# trans48.net
KiCad netlist of a schematic drawn in EAGLE
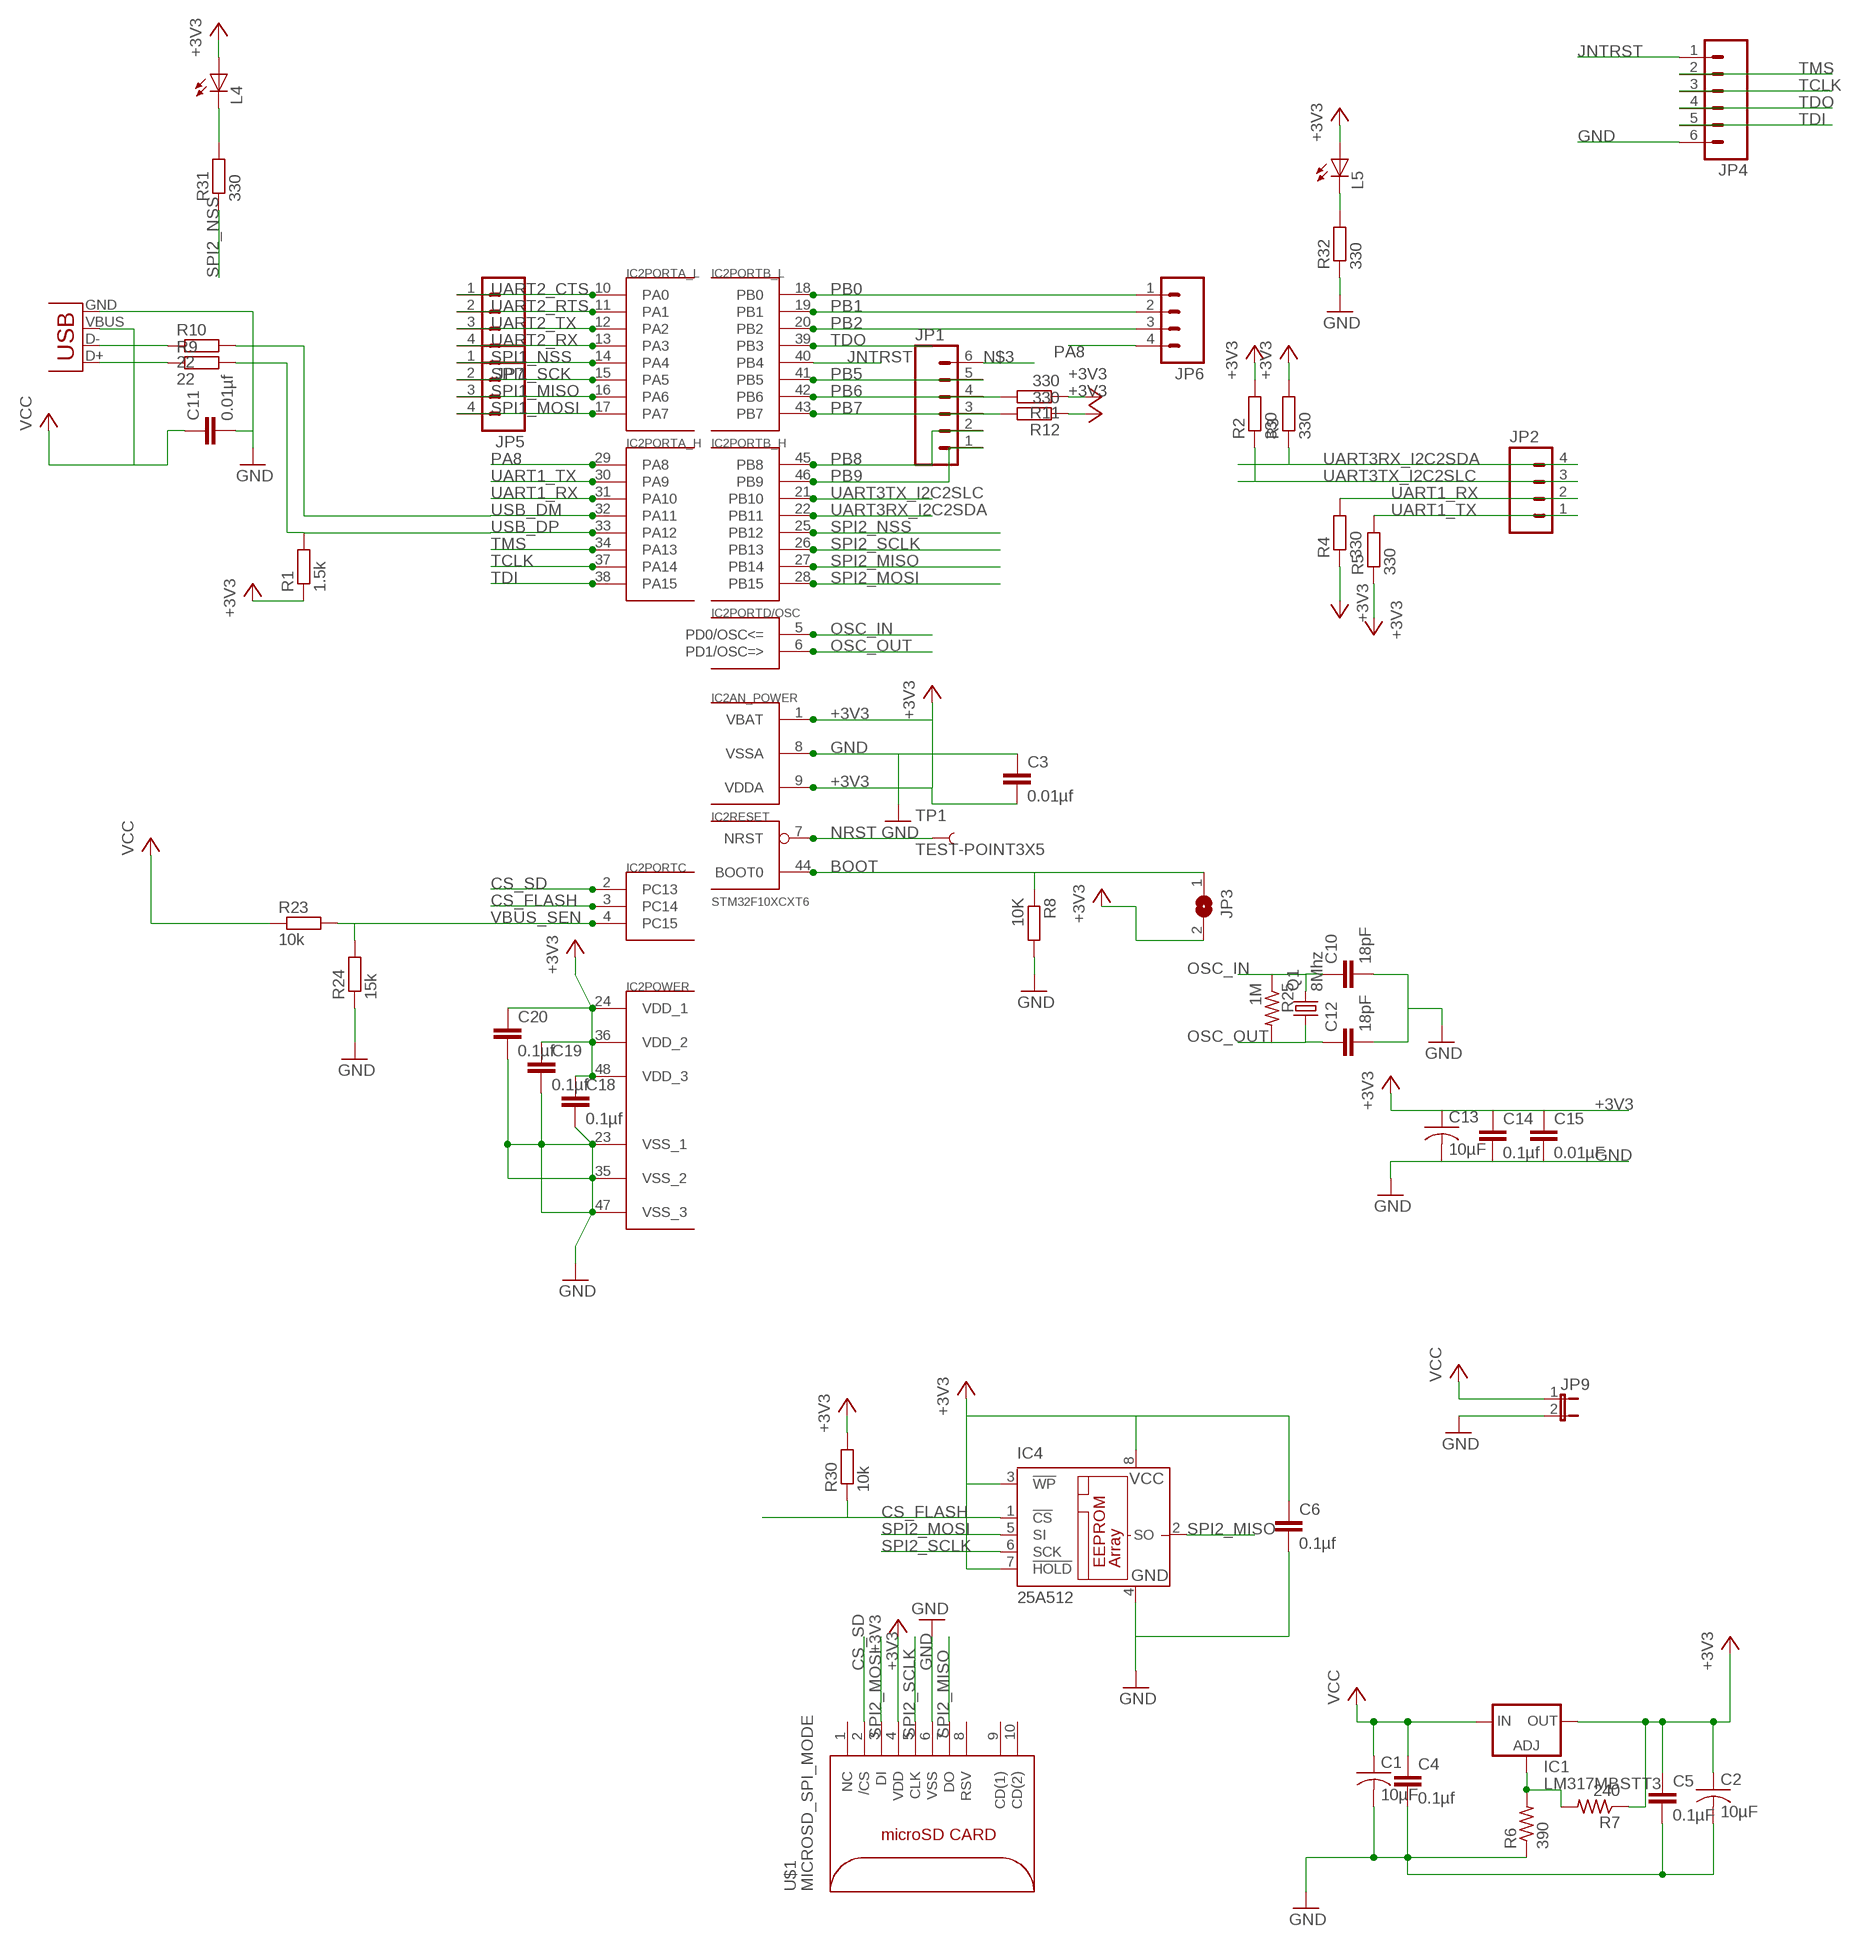
[diagram p0: schematic, sheet 1]

(export (version "E")
  (design (tool "Eeschema 10.0.6"))
  (components
    (comp (ref "C1")
      (value "10µF")
      (footprint "eagle-import:C1206")
      (libsource (lib "eagle-import") (part "C-USC1206"))
    )
    (comp (ref "C2")
      (value "10µF")
      (footprint "eagle-import:C1206")
      (libsource (lib "eagle-import") (part "C-USC1206"))
    )
    (comp (ref "C3")
      (value "0.01µf")
      (footprint "eagle-import:C0402")
      (libsource (lib "eagle-import") (part "C-EUC0402"))
    )
    (comp (ref "C4")
      (value "0.1µf")
      (footprint "eagle-import:C0402")
      (libsource (lib "eagle-import") (part "C-EUC0402"))
    )
    (comp (ref "C5")
      (value "0.1µF")
      (footprint "eagle-import:C0402")
      (libsource (lib "eagle-import") (part "C-EUC0402"))
    )
    (comp (ref "C6")
      (value "0.1µf")
      (footprint "eagle-import:C0402")
      (libsource (lib "eagle-import") (part "C-EUC0402"))
    )
    (comp (ref "C10")
      (value "18pF")
      (footprint "eagle-import:C0603")
      (libsource (lib "eagle-import") (part "C-EUC0603"))
    )
    (comp (ref "C11")
      (value "0.01µf")
      (footprint "eagle-import:C0402")
      (libsource (lib "eagle-import") (part "C-EUC0402"))
    )
    (comp (ref "C12")
      (value "18pF")
      (footprint "eagle-import:C0603")
      (libsource (lib "eagle-import") (part "C-EUC0603"))
    )
    (comp (ref "C13")
      (value "10µF")
      (footprint "eagle-import:C1206")
      (libsource (lib "eagle-import") (part "C-USC1206"))
    )
    (comp (ref "C14")
      (value "0.1µf")
      (footprint "eagle-import:C0603")
      (libsource (lib "eagle-import") (part "C-EUC0603"))
    )
    (comp (ref "C15")
      (value "0.01µF")
      (footprint "eagle-import:C0603")
      (libsource (lib "eagle-import") (part "C-EUC0603"))
    )
    (comp (ref "C18")
      (value "0.1µf")
      (footprint "eagle-import:C0402")
      (libsource (lib "eagle-import") (part "C-EUC0402"))
    )
    (comp (ref "C19")
      (value "0.1µf")
      (footprint "eagle-import:C0402")
      (libsource (lib "eagle-import") (part "C-EUC0402"))
    )
    (comp (ref "C20")
      (value "0.1µf")
      (footprint "eagle-import:C0402")
      (libsource (lib "eagle-import") (part "C-EUC0402"))
    )
    (comp (ref "IC1")
      (value "LM317MBSTT3")
      (footprint "eagle-import:SOT223")
      (libsource (lib "eagle-import") (part "LM317?MBSTT3"))
    )
    (comp (ref "IC2")
      (value "STM32F10XCXT6")
      (footprint "eagle-import:TQFP48")
      (libsource (lib "eagle-import") (part "STM32F10XCXT6"))
    )
    (comp (ref "IC4")
      (value "25A512")
      (footprint "eagle-import:SO-08")
      (libsource (lib "eagle-import") (part "25SNAA080"))
    )
    (comp (ref "JP1")
      (value "M06EM406")
      (footprint "eagle-import:EM406")
      (libsource (lib "eagle-import") (part "M06EM406"))
    )
    (comp (ref "JP2")
      (value "M04SMD2")
      (footprint "eagle-import:1X04-1MM-RA")
      (libsource (lib "eagle-import") (part "M04SMD2"))
    )
    (comp (ref "JP3") (value "SJ") (footprint "eagle-import:SJ") (libsource (lib "eagle-import") (part "SJ")))
    (comp (ref "JP4")
      (value "M06EM406")
      (footprint "eagle-import:EM406")
      (libsource (lib "eagle-import") (part "M06EM406"))
    )
    (comp (ref "JP5")
      (value "M04SMD2")
      (footprint "eagle-import:1X04-1MM-RA")
      (libsource (lib "eagle-import") (part "M04SMD2"))
    )
    (comp (ref "JP6")
      (value "M04SMD2")
      (footprint "eagle-import:1X04-1MM-RA")
      (libsource (lib "eagle-import") (part "M04SMD2"))
    )
    (comp (ref "JP7")
      (value "M04SMD2")
      (footprint "eagle-import:1X04-1MM-RA")
      (libsource (lib "eagle-import") (part "M04SMD2"))
    )
    (comp (ref "JP9")
      (value "JUMPER-2SMD-NO-NS")
      (footprint "eagle-import:SJ_2S-NO-NS")
      (libsource (lib "eagle-import") (part "JUMPER-2SMD-NO-NS"))
    )
    (comp (ref "L4")
      (value "LEDSML0603")
      (footprint "eagle-import:SML0603")
      (libsource (lib "eagle-import") (part "LEDSML0603"))
    )
    (comp (ref "L5")
      (value "LEDSML0603")
      (footprint "eagle-import:SML0603")
      (libsource (lib "eagle-import") (part "LEDSML0603"))
    )
    (comp (ref "Q1")
      (value "8Mhz")
      (footprint "eagle-import:SM49")
      (libsource (lib "eagle-import") (part "CRYSTALSM49"))
    )
    (comp (ref "R1")
      (value "1.5k")
      (footprint "eagle-import:R0402")
      (libsource (lib "eagle-import") (part "R-EU_R0402"))
    )
    (comp (ref "R2")
      (value "330")
      (footprint "eagle-import:R0402")
      (libsource (lib "eagle-import") (part "R-EU_R0402"))
    )
    (comp (ref "R3")
      (value "330")
      (footprint "eagle-import:R0402")
      (libsource (lib "eagle-import") (part "R-EU_R0402"))
    )
    (comp (ref "R4")
      (value "330")
      (footprint "eagle-import:R0402")
      (libsource (lib "eagle-import") (part "R-EU_R0402"))
    )
    (comp (ref "R5")
      (value "330")
      (footprint "eagle-import:R0402")
      (libsource (lib "eagle-import") (part "R-EU_R0402"))
    )
    (comp (ref "R6")
      (value "390")
      (footprint "eagle-import:R0603")
      (libsource (lib "eagle-import") (part "R-US_R0603"))
    )
    (comp (ref "R7")
      (value "240")
      (footprint "eagle-import:R0603")
      (libsource (lib "eagle-import") (part "R-US_R0603"))
    )
    (comp (ref "R8")
      (value "10K")
      (footprint "eagle-import:R0402")
      (libsource (lib "eagle-import") (part "R-EU_R0402"))
    )
    (comp (ref "R9")
      (value "22")
      (footprint "eagle-import:R0402")
      (libsource (lib "eagle-import") (part "R-EU_R0402"))
    )
    (comp (ref "R10")
      (value "22")
      (footprint "eagle-import:R0402")
      (libsource (lib "eagle-import") (part "R-EU_R0402"))
    )
    (comp (ref "R11")
      (value "330")
      (footprint "eagle-import:R0402")
      (libsource (lib "eagle-import") (part "R-EU_R0402"))
    )
    (comp (ref "R12")
      (value "330")
      (footprint "eagle-import:R0402")
      (libsource (lib "eagle-import") (part "R-EU_R0402"))
    )
    (comp (ref "R23")
      (value "10k")
      (footprint "eagle-import:R0402")
      (libsource (lib "eagle-import") (part "R-EU_R0402"))
    )
    (comp (ref "R24")
      (value "15k")
      (footprint "eagle-import:R0402")
      (libsource (lib "eagle-import") (part "R-EU_R0402"))
    )
    (comp (ref "R25")
      (value "1M")
      (footprint "eagle-import:R0603")
      (libsource (lib "eagle-import") (part "R-US_R0603"))
    )
    (comp (ref "R30")
      (value "10k")
      (footprint "eagle-import:R0402")
      (libsource (lib "eagle-import") (part "R-EU_R0402"))
    )
    (comp (ref "R31")
      (value "330")
      (footprint "eagle-import:R0402")
      (libsource (lib "eagle-import") (part "R-EU_R0402"))
    )
    (comp (ref "R32")
      (value "330")
      (footprint "eagle-import:R0402")
      (libsource (lib "eagle-import") (part "R-EU_R0402"))
    )
    (comp (ref "TP1")
      (value "TEST-POINT3X5")
      (footprint "eagle-import:PAD.03X.05")
      (libsource (lib "eagle-import") (part "TEST-POINT3X5"))
    )
    (comp (ref "U$1")
      (value "MICROSD_SPI_MODE")
      (footprint "eagle-import:MICRO_SD_CONNECTOR")
      (libsource (lib "eagle-import") (part "MICROSD_SPI_MODE"))
    )
    (comp (ref "X1")
      (value "USB-MICROB")
      (footprint "eagle-import:USB-MICROB")
      (libsource (lib "eagle-import") (part "USB-MICROB"))
    )
  )
  (nets
    (net (code "1") (name "+3V3") (class "Default")
      (node (ref "C13") (pin "1") (pinfunction "1_1") (pintype "passive"))
      (node (ref "C14") (pin "1") (pinfunction "1_1") (pintype "passive"))
      (node (ref "C15") (pin "1") (pinfunction "1_1") (pintype "passive"))
      (node (ref "C18") (pin "1") (pinfunction "1_1") (pintype "passive"))
      (node (ref "C19") (pin "1") (pinfunction "1_1") (pintype "passive"))
      (node (ref "C2") (pin "1") (pinfunction "1_1") (pintype "passive"))
      (node (ref "C20") (pin "1") (pinfunction "1_1") (pintype "passive"))
      (node (ref "C3") (pin "2") (pinfunction "2_2") (pintype "passive"))
      (node (ref "C5") (pin "1") (pinfunction "1_1") (pintype "passive"))
      (node (ref "C6") (pin "1") (pinfunction "1_1") (pintype "passive"))
      (node (ref "IC1") (pin "4") (pinfunction "OUT_4") (pintype "passive"))
      (node (ref "IC2") (pin "1") (pinfunction "VBAT_1") (pintype "power_in"))
      (node (ref "IC2") (pin "24") (pinfunction "VDD_1_24") (pintype "power_in"))
      (node (ref "IC2") (pin "36") (pinfunction "VDD_2_36") (pintype "power_in"))
      (node (ref "IC2") (pin "48") (pinfunction "VDD_3_48") (pintype "power_in"))
      (node (ref "IC2") (pin "9") (pinfunction "VDDA_9") (pintype "power_in"))
      (node (ref "IC4") (pin "3") (pinfunction "~{WP}_3") (pintype "input"))
      (node (ref "IC4") (pin "7") (pinfunction "~{HOLD}_7") (pintype "input"))
      (node (ref "IC4") (pin "8") (pinfunction "VCC_8") (pintype "power_in"))
      (node (ref "JP3") (pin "2") (pinfunction "2_2") (pintype "passive"))
      (node (ref "L4") (pin "A") (pinfunction "A_A") (pintype "passive"))
      (node (ref "L5") (pin "A") (pinfunction "A_A") (pintype "passive"))
      (node (ref "R1") (pin "1") (pinfunction "1_1") (pintype "passive"))
      (node (ref "R11") (pin "1") (pinfunction "1_1") (pintype "passive"))
      (node (ref "R12") (pin "1") (pinfunction "1_1") (pintype "passive"))
      (node (ref "R2") (pin "2") (pinfunction "2_2") (pintype "passive"))
      (node (ref "R3") (pin "2") (pinfunction "2_2") (pintype "passive"))
      (node (ref "R30") (pin "2") (pinfunction "2_2") (pintype "passive"))
      (node (ref "R4") (pin "1") (pinfunction "1_1") (pintype "passive"))
      (node (ref "R5") (pin "1") (pinfunction "1_1") (pintype "passive"))
      (node (ref "R7") (pin "1") (pinfunction "1_1") (pintype "passive"))
      (node (ref "U$1") (pin "4") (pinfunction "VDD_4") (pintype "bidirectional"))
    )
    (net (code "2") (name "/BOOT") (class "Default")
      (node (ref "IC2") (pin "44") (pinfunction "BOOT0_44") (pintype "input"))
      (node (ref "JP3") (pin "1") (pinfunction "1_1") (pintype "passive"))
      (node (ref "R8") (pin "1") (pinfunction "1_1") (pintype "passive"))
    )
    (net (code "3") (name "/CS_FLASH") (class "Default")
      (node (ref "IC2") (pin "3") (pinfunction "PC14_3") (pintype "bidirectional"))
      (node (ref "IC4") (pin "1") (pinfunction "~{CS}_1") (pintype "input"))
      (node (ref "R30") (pin "1") (pinfunction "1_1") (pintype "passive"))
    )
    (net (code "4") (name "/CS_SD") (class "Default")
      (node (ref "IC2") (pin "2") (pinfunction "PC13_2") (pintype "bidirectional"))
      (node (ref "U$1") (pin "2") (pinfunction "/CS_2") (pintype "bidirectional"))
    )
    (net (code "5") (name "/JNTRST") (class "Default")
      (node (ref "IC2") (pin "40") (pinfunction "PB4_40") (pintype "bidirectional"))
      (node (ref "JP4") (pin "1") (pinfunction "1_1") (pintype "passive"))
    )
    (net (code "6") (name "/N$3") (class "Default")
      (node (ref "JP1") (pin "6") (pinfunction "6_6") (pintype "passive"))
    )
    (net (code "7") (name "/NRST") (class "Default")
      (node (ref "IC2") (pin "7") (pinfunction "NRST_7") (pintype "input"))
      (node (ref "TP1") (pin "P$1") (pinfunction "1_P$1") (pintype "bidirectional"))
    )
    (net (code "8") (name "/OSC_IN") (class "Default")
      (node (ref "C10") (pin "1") (pinfunction "1_1") (pintype "passive"))
      (node (ref "IC2") (pin "5") (pinfunction "PD0/OSC<=_5") (pintype "bidirectional"))
      (node (ref "Q1") (pin "2") (pinfunction "2_2") (pintype "passive"))
      (node (ref "R25") (pin "1") (pinfunction "1_1") (pintype "passive"))
    )
    (net (code "9") (name "/OSC_OUT") (class "Default")
      (node (ref "C12") (pin "1") (pinfunction "1_1") (pintype "passive"))
      (node (ref "IC2") (pin "6") (pinfunction "PD1/OSC=>_6") (pintype "bidirectional"))
      (node (ref "Q1") (pin "1") (pinfunction "1_1") (pintype "passive"))
      (node (ref "R25") (pin "2") (pinfunction "2_2") (pintype "passive"))
    )
    (net (code "10") (name "/PA8") (class "Default")
      (node (ref "IC2") (pin "29") (pinfunction "PA8_29") (pintype "bidirectional"))
      (node (ref "JP6") (pin "4") (pinfunction "4_4") (pintype "passive"))
    )
    (net (code "11") (name "/PB0") (class "Default")
      (node (ref "IC2") (pin "18") (pinfunction "PB0_18") (pintype "bidirectional"))
      (node (ref "JP6") (pin "1") (pinfunction "1_1") (pintype "passive"))
    )
    (net (code "12") (name "/PB1") (class "Default")
      (node (ref "IC2") (pin "19") (pinfunction "PB1_19") (pintype "bidirectional"))
      (node (ref "JP6") (pin "2") (pinfunction "2_2") (pintype "passive"))
    )
    (net (code "13") (name "/PB2") (class "Default")
      (node (ref "IC2") (pin "20") (pinfunction "PB2_20") (pintype "bidirectional"))
      (node (ref "JP6") (pin "3") (pinfunction "3_3") (pintype "passive"))
    )
    (net (code "14") (name "/PB5") (class "Default")
      (node (ref "IC2") (pin "41") (pinfunction "PB5_41") (pintype "bidirectional"))
      (node (ref "JP1") (pin "5") (pinfunction "5_5") (pintype "passive"))
    )
    (net (code "15") (name "/PB6") (class "Default")
      (node (ref "IC2") (pin "42") (pinfunction "PB6_42") (pintype "bidirectional"))
      (node (ref "JP1") (pin "4") (pinfunction "4_4") (pintype "passive"))
      (node (ref "R11") (pin "2") (pinfunction "2_2") (pintype "passive"))
    )
    (net (code "16") (name "/PB7") (class "Default")
      (node (ref "IC2") (pin "43") (pinfunction "PB7_43") (pintype "bidirectional"))
      (node (ref "JP1") (pin "3") (pinfunction "3_3") (pintype "passive"))
      (node (ref "R12") (pin "2") (pinfunction "2_2") (pintype "passive"))
    )
    (net (code "17") (name "/PB8") (class "Default")
      (node (ref "IC2") (pin "45") (pinfunction "PB8_45") (pintype "bidirectional"))
      (node (ref "JP1") (pin "2") (pinfunction "2_2") (pintype "passive"))
    )
    (net (code "18") (name "/PB9") (class "Default")
      (node (ref "IC2") (pin "46") (pinfunction "PB9_46") (pintype "bidirectional"))
      (node (ref "JP1") (pin "1") (pinfunction "1_1") (pintype "passive"))
    )
    (net (code "19") (name "/SPI1_MISO") (class "Default")
      (node (ref "IC2") (pin "16") (pinfunction "PA6_16") (pintype "bidirectional"))
      (node (ref "JP5") (pin "3") (pinfunction "3_3") (pintype "passive"))
    )
    (net (code "20") (name "/SPI1_MOSI") (class "Default")
      (node (ref "IC2") (pin "17") (pinfunction "PA7_17") (pintype "bidirectional"))
      (node (ref "JP5") (pin "4") (pinfunction "4_4") (pintype "passive"))
    )
    (net (code "21") (name "/SPI1_NSS") (class "Default")
      (node (ref "IC2") (pin "14") (pinfunction "PA4_14") (pintype "bidirectional"))
      (node (ref "JP5") (pin "1") (pinfunction "1_1") (pintype "passive"))
    )
    (net (code "22") (name "/SPI1_SCK") (class "Default")
      (node (ref "IC2") (pin "15") (pinfunction "PA5_15") (pintype "bidirectional"))
      (node (ref "JP5") (pin "2") (pinfunction "2_2") (pintype "passive"))
    )
    (net (code "23") (name "/SPI2_MISO") (class "Default")
      (node (ref "IC2") (pin "27") (pinfunction "PB14_27") (pintype "bidirectional"))
      (node (ref "IC4") (pin "2") (pinfunction "SO_2") (pintype "bidirectional"))
      (node (ref "U$1") (pin "7") (pinfunction "DO_7") (pintype "bidirectional"))
    )
    (net (code "24") (name "/SPI2_MOSI") (class "Default")
      (node (ref "IC2") (pin "28") (pinfunction "PB15_28") (pintype "bidirectional"))
      (node (ref "IC4") (pin "5") (pinfunction "SI_5") (pintype "input"))
      (node (ref "U$1") (pin "3") (pinfunction "DI_3") (pintype "bidirectional"))
    )
    (net (code "25") (name "/SPI2_NSS") (class "Default")
      (node (ref "IC2") (pin "25") (pinfunction "PB12_25") (pintype "bidirectional"))
      (node (ref "R31") (pin "1") (pinfunction "1_1") (pintype "passive"))
    )
    (net (code "26") (name "/SPI2_SCLK") (class "Default")
      (node (ref "IC2") (pin "26") (pinfunction "PB13_26") (pintype "bidirectional"))
      (node (ref "IC4") (pin "6") (pinfunction "SCK_6") (pintype "input"))
      (node (ref "U$1") (pin "5") (pinfunction "CLK_5") (pintype "bidirectional"))
    )
    (net (code "27") (name "/TCLK") (class "Default")
      (node (ref "IC2") (pin "37") (pinfunction "PA14_37") (pintype "bidirectional"))
      (node (ref "JP4") (pin "3") (pinfunction "3_3") (pintype "passive"))
    )
    (net (code "28") (name "/TDI") (class "Default")
      (node (ref "IC2") (pin "38") (pinfunction "PA15_38") (pintype "bidirectional"))
      (node (ref "JP4") (pin "5") (pinfunction "5_5") (pintype "passive"))
    )
    (net (code "29") (name "/TDO") (class "Default")
      (node (ref "IC2") (pin "39") (pinfunction "PB3_39") (pintype "bidirectional"))
      (node (ref "JP4") (pin "4") (pinfunction "4_4") (pintype "passive"))
    )
    (net (code "30") (name "/TMS") (class "Default")
      (node (ref "IC2") (pin "34") (pinfunction "PA13_34") (pintype "bidirectional"))
      (node (ref "JP4") (pin "2") (pinfunction "2_2") (pintype "passive"))
    )
    (net (code "31") (name "/UART1_RX") (class "Default")
      (node (ref "IC2") (pin "31") (pinfunction "PA10_31") (pintype "bidirectional"))
      (node (ref "JP2") (pin "2") (pinfunction "2_2") (pintype "passive"))
      (node (ref "R4") (pin "2") (pinfunction "2_2") (pintype "passive"))
    )
    (net (code "32") (name "/UART1_TX") (class "Default")
      (node (ref "IC2") (pin "30") (pinfunction "PA9_30") (pintype "bidirectional"))
      (node (ref "JP2") (pin "1") (pinfunction "1_1") (pintype "passive"))
      (node (ref "R5") (pin "2") (pinfunction "2_2") (pintype "passive"))
    )
    (net (code "33") (name "/UART2_CTS") (class "Default")
      (node (ref "IC2") (pin "10") (pinfunction "PA0_10") (pintype "bidirectional"))
      (node (ref "JP7") (pin "1") (pinfunction "1_1") (pintype "passive"))
    )
    (net (code "34") (name "/UART2_RTS") (class "Default")
      (node (ref "IC2") (pin "11") (pinfunction "PA1_11") (pintype "bidirectional"))
      (node (ref "JP7") (pin "2") (pinfunction "2_2") (pintype "passive"))
    )
    (net (code "35") (name "/UART2_RX") (class "Default")
      (node (ref "IC2") (pin "13") (pinfunction "PA3_13") (pintype "bidirectional"))
      (node (ref "JP7") (pin "4") (pinfunction "4_4") (pintype "passive"))
    )
    (net (code "36") (name "/UART2_TX") (class "Default")
      (node (ref "IC2") (pin "12") (pinfunction "PA2_12") (pintype "bidirectional"))
      (node (ref "JP7") (pin "3") (pinfunction "3_3") (pintype "passive"))
    )
    (net (code "37") (name "/UART3RX_I2C2SDA") (class "Default")
      (node (ref "IC2") (pin "22") (pinfunction "PB11_22") (pintype "bidirectional"))
      (node (ref "JP2") (pin "4") (pinfunction "4_4") (pintype "passive"))
      (node (ref "R3") (pin "1") (pinfunction "1_1") (pintype "passive"))
    )
    (net (code "38") (name "/UART3TX_I2C2SLC") (class "Default")
      (node (ref "IC2") (pin "21") (pinfunction "PB10_21") (pintype "bidirectional"))
      (node (ref "JP2") (pin "3") (pinfunction "3_3") (pintype "passive"))
      (node (ref "R2") (pin "1") (pinfunction "1_1") (pintype "passive"))
    )
    (net (code "39") (name "/USB_DM") (class "Default")
      (node (ref "IC2") (pin "32") (pinfunction "PA11_32") (pintype "bidirectional"))
      (node (ref "R10") (pin "2") (pinfunction "2_2") (pintype "passive"))
    )
    (net (code "40") (name "/USB_DP") (class "Default")
      (node (ref "IC2") (pin "33") (pinfunction "PA12_33") (pintype "bidirectional"))
      (node (ref "R1") (pin "2") (pinfunction "2_2") (pintype "passive"))
      (node (ref "R9") (pin "2") (pinfunction "2_2") (pintype "passive"))
    )
    (net (code "41") (name "/VBUS_SEN") (class "Default")
      (node (ref "IC2") (pin "4") (pinfunction "PC15_4") (pintype "bidirectional"))
      (node (ref "R23") (pin "2") (pinfunction "2_2") (pintype "passive"))
      (node (ref "R24") (pin "2") (pinfunction "2_2") (pintype "passive"))
    )
    (net (code "42") (name "GND") (class "Default")
      (node (ref "C1") (pin "2") (pinfunction "2_2") (pintype "passive"))
      (node (ref "C10") (pin "2") (pinfunction "2_2") (pintype "passive"))
      (node (ref "C11") (pin "2") (pinfunction "2_2") (pintype "passive"))
      (node (ref "C12") (pin "2") (pinfunction "2_2") (pintype "passive"))
      (node (ref "C13") (pin "2") (pinfunction "2_2") (pintype "passive"))
      (node (ref "C14") (pin "2") (pinfunction "2_2") (pintype "passive"))
      (node (ref "C15") (pin "2") (pinfunction "2_2") (pintype "passive"))
      (node (ref "C18") (pin "2") (pinfunction "2_2") (pintype "passive"))
      (node (ref "C19") (pin "2") (pinfunction "2_2") (pintype "passive"))
      (node (ref "C2") (pin "2") (pinfunction "2_2") (pintype "passive"))
      (node (ref "C20") (pin "2") (pinfunction "2_2") (pintype "passive"))
      (node (ref "C3") (pin "1") (pinfunction "1_1") (pintype "passive"))
      (node (ref "C4") (pin "2") (pinfunction "2_2") (pintype "passive"))
      (node (ref "C5") (pin "2") (pinfunction "2_2") (pintype "passive"))
      (node (ref "C6") (pin "2") (pinfunction "2_2") (pintype "passive"))
      (node (ref "IC2") (pin "23") (pinfunction "VSS_1_23") (pintype "power_in"))
      (node (ref "IC2") (pin "35") (pinfunction "VSS_2_35") (pintype "power_in"))
      (node (ref "IC2") (pin "47") (pinfunction "VSS_3_47") (pintype "power_in"))
      (node (ref "IC2") (pin "8") (pinfunction "VSSA_8") (pintype "power_in"))
      (node (ref "IC4") (pin "4") (pinfunction "GND_4") (pintype "power_in"))
      (node (ref "JP4") (pin "6") (pinfunction "6_6") (pintype "passive"))
      (node (ref "JP9") (pin "2") (pinfunction "2_2") (pintype "passive"))
      (node (ref "R24") (pin "1") (pinfunction "1_1") (pintype "passive"))
      (node (ref "R32") (pin "1") (pinfunction "1_1") (pintype "passive"))
      (node (ref "R6") (pin "1") (pinfunction "1_1") (pintype "passive"))
      (node (ref "R8") (pin "2") (pinfunction "2_2") (pintype "passive"))
      (node (ref "U$1") (pin "6") (pinfunction "VSS_6") (pintype "bidirectional"))
      (node (ref "X1") (pin "GND") (pinfunction "GND_GND") (pintype "bidirectional"))
    )
    (net (code "43") (name "Net-(IC1-ADJ)") (class "Default")
      (node (ref "IC1") (pin "1") (pinfunction "ADJ_1") (pintype "input"))
      (node (ref "R6") (pin "2") (pinfunction "2_2") (pintype "passive"))
      (node (ref "R7") (pin "2") (pinfunction "2_2") (pintype "passive"))
    )
    (net (code "44") (name "Net-(L4-PadC)") (class "Default")
      (node (ref "L4") (pin "C") (pinfunction "C_C") (pintype "passive"))
      (node (ref "R31") (pin "2") (pinfunction "2_2") (pintype "passive"))
    )
    (net (code "45") (name "Net-(L5-PadC)") (class "Default")
      (node (ref "L5") (pin "C") (pinfunction "C_C") (pintype "passive"))
      (node (ref "R32") (pin "2") (pinfunction "2_2") (pintype "passive"))
    )
    (net (code "46") (name "Net-(R9-Pad1)") (class "Default")
      (node (ref "R9") (pin "1") (pinfunction "1_1") (pintype "passive"))
      (node (ref "X1") (pin "D+") (pinfunction "D+_D+") (pintype "bidirectional"))
    )
    (net (code "47") (name "Net-(R10-Pad1)") (class "Default")
      (node (ref "R10") (pin "1") (pinfunction "1_1") (pintype "passive"))
      (node (ref "X1") (pin "D-") (pinfunction "D-_D-") (pintype "bidirectional"))
    )
    (net (code "48") (name "VCC") (class "Default")
      (node (ref "C1") (pin "1") (pinfunction "1_1") (pintype "passive"))
      (node (ref "C11") (pin "1") (pinfunction "1_1") (pintype "passive"))
      (node (ref "C4") (pin "1") (pinfunction "1_1") (pintype "passive"))
      (node (ref "IC1") (pin "3") (pinfunction "IN_3") (pintype "input"))
      (node (ref "JP9") (pin "1") (pinfunction "1_1") (pintype "passive"))
      (node (ref "R23") (pin "1") (pinfunction "1_1") (pintype "passive"))
      (node (ref "X1") (pin "VBUS") (pinfunction "VBUS_VBUS") (pintype "bidirectional"))
    )
    (net (code "49") (name "unconnected-(U$1-CD(1)-Pad9)") (class "Default")
      (node (ref "U$1") (pin "9") (pinfunction "CD(1)_9") (pintype "bidirectional"))
    )
    (net (code "50") (name "unconnected-(U$1-CD(2)-Pad10)") (class "Default")
      (node (ref "U$1") (pin "10") (pinfunction "CD(2)_10") (pintype "bidirectional"))
    )
    (net (code "51") (name "unconnected-(U$1-NC-Pad1)") (class "Default")
      (node (ref "U$1") (pin "1") (pinfunction "NC_1") (pintype "bidirectional"))
    )
    (net (code "52") (name "unconnected-(U$1-RSV-Pad8)") (class "Default")
      (node (ref "U$1") (pin "8") (pinfunction "RSV_8") (pintype "bidirectional"))
    )
  )
)
